# iDAC1.net
KiCad netlist of a schematic drawn in Altium Designer
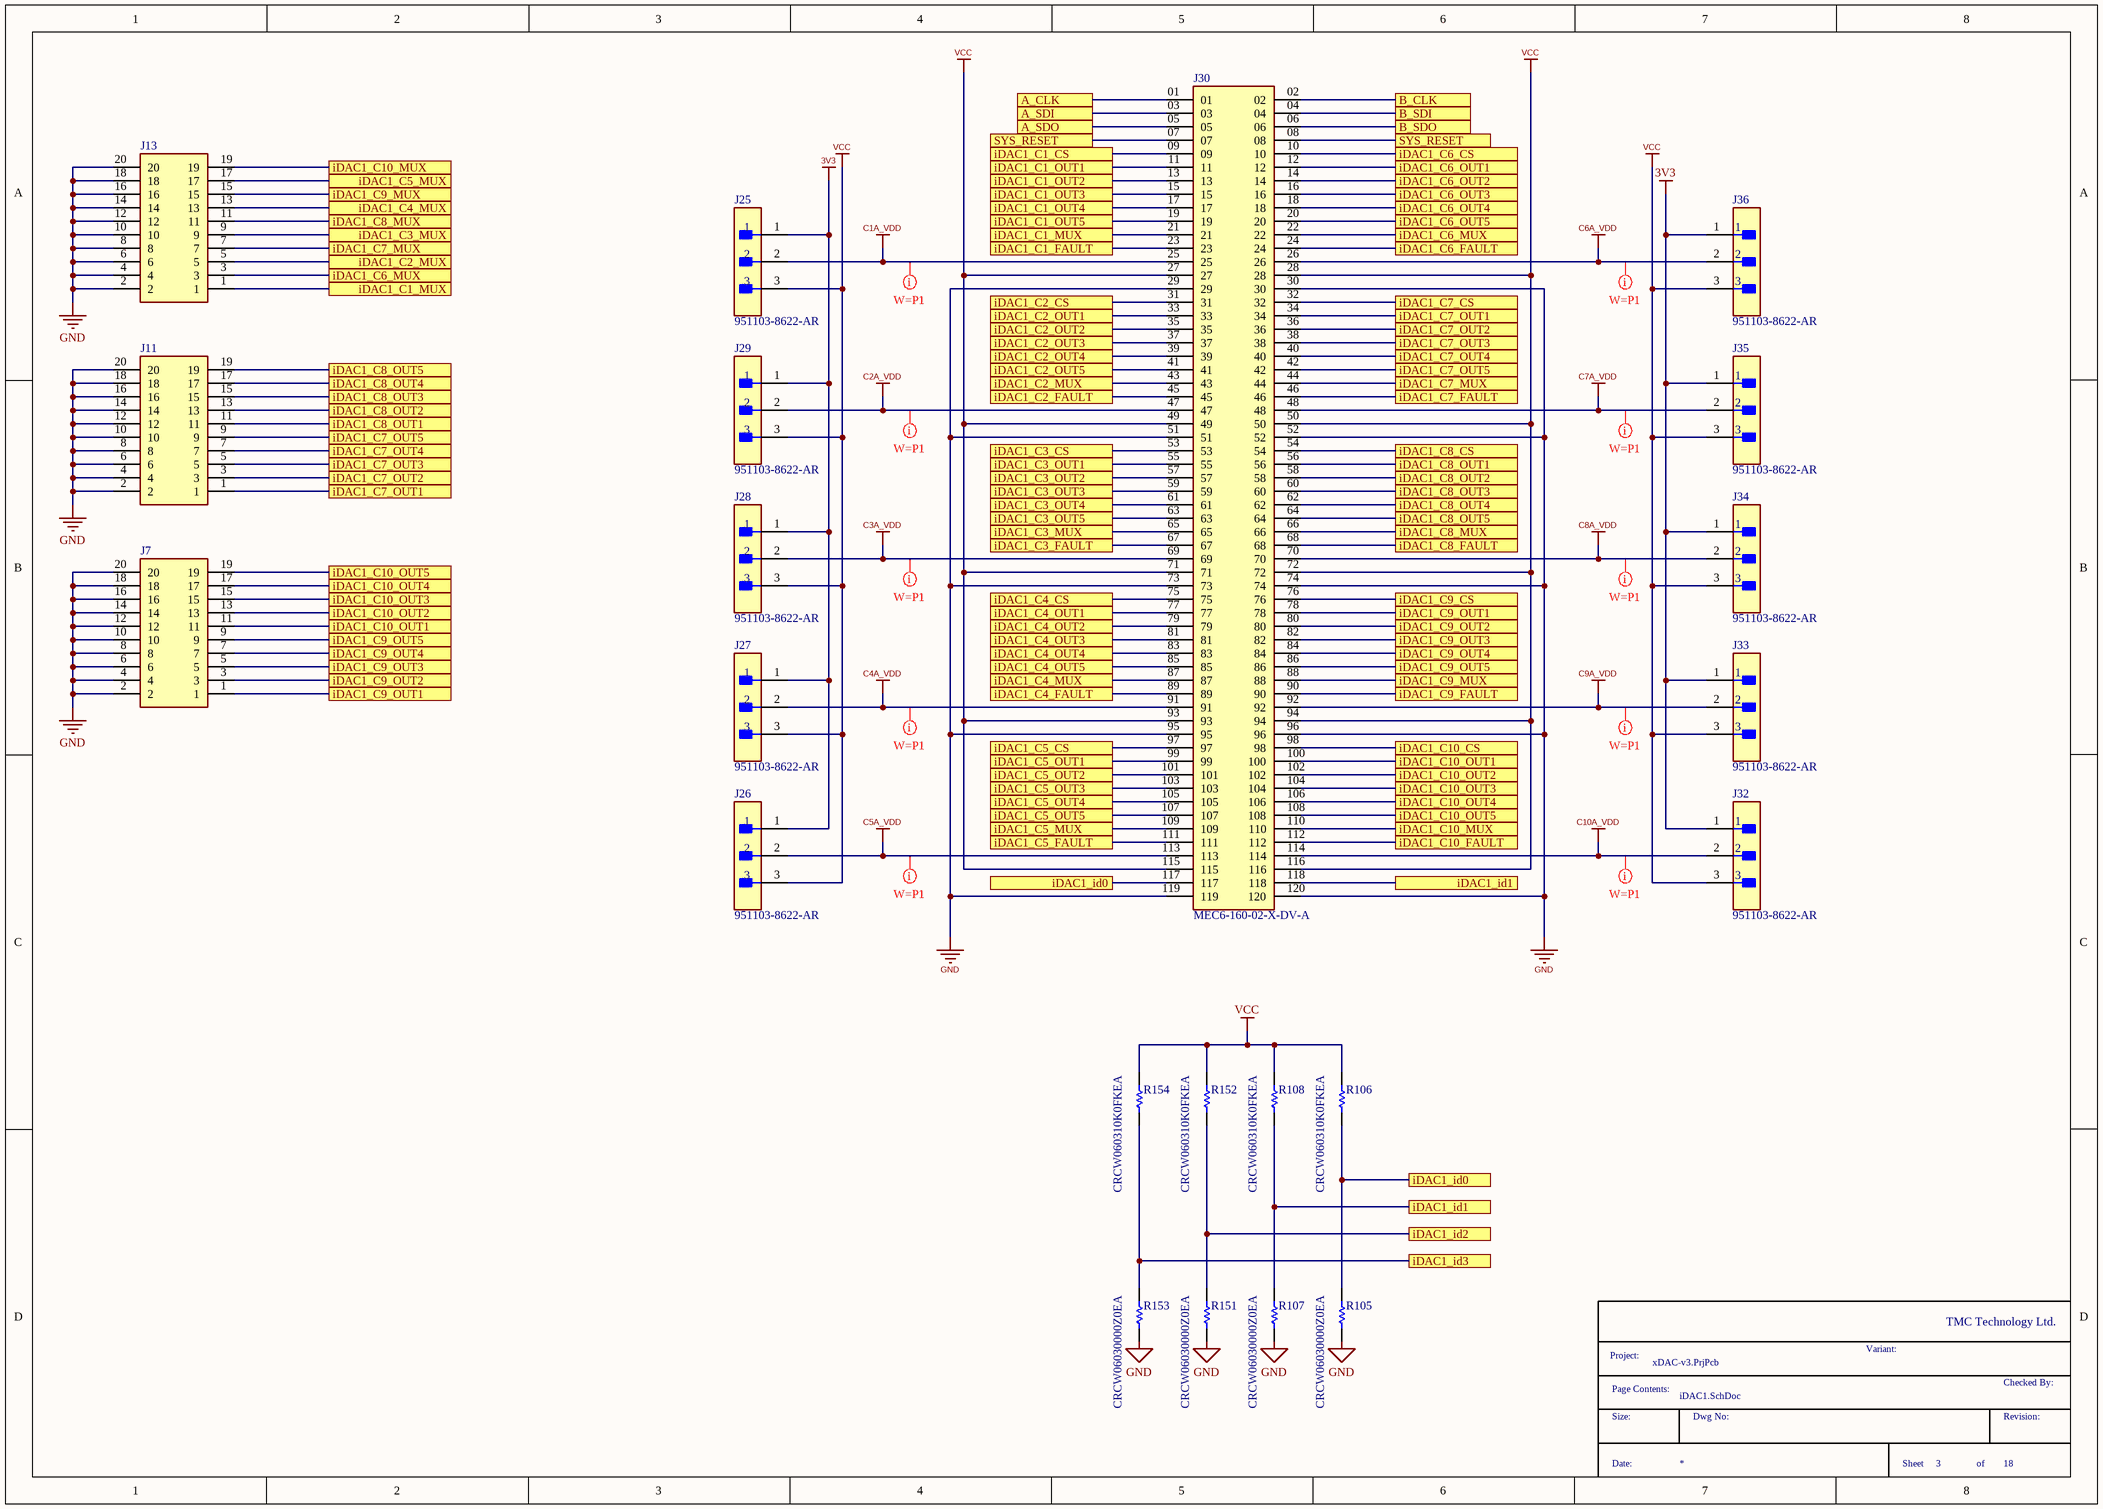
[diagram p0: iDAC1.SchDoc]

(export (version "E")
  (design (tool "Eeschema 10.0.6"))
  (components
    (comp (ref "J7")
      (value "~")
      (footprint "HDRV20W40P127_2X10_1270X340X550P")
      (description "Connector")
      (fields (field (name "MANUFACTURER_PART_NUMBER") "20021111-00020T4LF"))
      (libsource (lib "xDAC_Carrier") (part "20021111-00020T4LF"))
    )
    (comp (ref "J11")
      (value "~")
      (footprint "HDRV20W40P127_2X10_1270X340X550P")
      (description "Connector")
      (fields (field (name "MANUFACTURER_PART_NUMBER") "20021111-00020T4LF"))
      (libsource (lib "xDAC_Carrier") (part "20021111-00020T4LF"))
    )
    (comp (ref "J13")
      (value "~")
      (footprint "HDRV20W40P127_2X10_1270X340X550P")
      (description "Connector")
      (fields (field (name "MANUFACTURER_PART_NUMBER") "20021111-00020T4LF"))
      (libsource (lib "xDAC_Carrier") (part "20021111-00020T4LF"))
    )
    (comp (ref "J25")
      (value "951103-8622-AR")
      (footprint "FP-951103-8622-AR-MFG")
      (description "CONN HEADER VERT 3POS 2MM")
      (fields
        (field (name "OCTOPART") "https://octopart.com/951103-8622-ar-3m-14400669")
        (field (name "MANUFACTURER") "3M")
      )
      (libsource (lib "xDAC_Carrier") (part "CMP-05379-000003-1"))
    )
    (comp (ref "J26")
      (value "951103-8622-AR")
      (footprint "FP-951103-8622-AR-MFG")
      (description "CONN HEADER VERT 3POS 2MM")
      (fields
        (field (name "OCTOPART") "https://octopart.com/951103-8622-ar-3m-14400669")
        (field (name "MANUFACTURER") "3M")
      )
      (libsource (lib "xDAC_Carrier") (part "CMP-05379-000003-1"))
    )
    (comp (ref "J27")
      (value "951103-8622-AR")
      (footprint "FP-951103-8622-AR-MFG")
      (description "CONN HEADER VERT 3POS 2MM")
      (fields
        (field (name "OCTOPART") "https://octopart.com/951103-8622-ar-3m-14400669")
        (field (name "MANUFACTURER") "3M")
      )
      (libsource (lib "xDAC_Carrier") (part "CMP-05379-000003-1"))
    )
    (comp (ref "J28")
      (value "951103-8622-AR")
      (footprint "FP-951103-8622-AR-MFG")
      (description "CONN HEADER VERT 3POS 2MM")
      (fields
        (field (name "OCTOPART") "https://octopart.com/951103-8622-ar-3m-14400669")
        (field (name "MANUFACTURER") "3M")
      )
      (libsource (lib "xDAC_Carrier") (part "CMP-05379-000003-1"))
    )
    (comp (ref "J29")
      (value "951103-8622-AR")
      (footprint "FP-951103-8622-AR-MFG")
      (description "CONN HEADER VERT 3POS 2MM")
      (fields
        (field (name "OCTOPART") "https://octopart.com/951103-8622-ar-3m-14400669")
        (field (name "MANUFACTURER") "3M")
      )
      (libsource (lib "xDAC_Carrier") (part "CMP-05379-000003-1"))
    )
    (comp (ref "J30")
      (value "MEC6-160-02-X-DV-A")
      (footprint "SAMTEC_MEC6-160-02-X-DV-A")
      (fields (field (name "MF") "Samtec Inc."))
      (libsource (lib "xDAC_Carrier") (part "MEC6-160-02-X-DV-A"))
    )
    (comp (ref "J32")
      (value "951103-8622-AR")
      (footprint "FP-951103-8622-AR-MFG")
      (description "CONN HEADER VERT 3POS 2MM")
      (fields
        (field (name "OCTOPART") "https://octopart.com/951103-8622-ar-3m-14400669")
        (field (name "MANUFACTURER") "3M")
      )
      (libsource (lib "") (part "CMP-05379-000003-1_1"))
    )
    (comp (ref "J33")
      (value "951103-8622-AR")
      (footprint "FP-951103-8622-AR-MFG")
      (description "CONN HEADER VERT 3POS 2MM")
      (fields
        (field (name "OCTOPART") "https://octopart.com/951103-8622-ar-3m-14400669")
        (field (name "MANUFACTURER") "3M")
      )
      (libsource (lib "") (part "CMP-05379-000003-1_1"))
    )
    (comp (ref "J34")
      (value "951103-8622-AR")
      (footprint "FP-951103-8622-AR-MFG")
      (description "CONN HEADER VERT 3POS 2MM")
      (fields
        (field (name "OCTOPART") "https://octopart.com/951103-8622-ar-3m-14400669")
        (field (name "MANUFACTURER") "3M")
      )
      (libsource (lib "") (part "CMP-05379-000003-1_1"))
    )
    (comp (ref "J35")
      (value "951103-8622-AR")
      (footprint "FP-951103-8622-AR-MFG")
      (description "CONN HEADER VERT 3POS 2MM")
      (fields
        (field (name "OCTOPART") "https://octopart.com/951103-8622-ar-3m-14400669")
        (field (name "MANUFACTURER") "3M")
      )
      (libsource (lib "") (part "CMP-05379-000003-1_1"))
    )
    (comp (ref "J36")
      (value "951103-8622-AR")
      (footprint "FP-951103-8622-AR-MFG")
      (description "CONN HEADER VERT 3POS 2MM")
      (fields
        (field (name "OCTOPART") "https://octopart.com/951103-8622-ar-3m-14400669")
        (field (name "MANUFACTURER") "3M")
      )
      (libsource (lib "") (part "CMP-05379-000003-1_1"))
    )
    (comp (ref "R105")
      (value "CRCW06030000Z0EA")
      (footprint "RESC1609X50X30NL8T20")
      (description "Chip Resistor, 0 Ohm, Jumper, 100 mW, -55 to 155 degC, 0603 (1608 Metric), RoHS, Tape and Reel")
      (fields (field (name "MANUFACTURER") "Vishay Semiconductor"))
      (libsource (lib "Altium Content Vault") (part "RES-2"))
    )
    (comp (ref "R106")
      (value "CRCW060310K0FKEA")
      (footprint "RESC1609X50X30NL8T20")
      (description "Chip Resistor, 10 KOhm, +/- 1%, 100 mW, -55 to 155 degC, 0603 (1608 Metric), RoHS, Tape and Reel")
      (fields (field (name "MANUFACTURER") "Vishay Semiconductor"))
      (libsource (lib "Altium Content Vault") (part "RES-2"))
    )
    (comp (ref "R107")
      (value "CRCW06030000Z0EA")
      (footprint "RESC1609X50X30NL8T20")
      (description "Chip Resistor, 0 Ohm, Jumper, 100 mW, -55 to 155 degC, 0603 (1608 Metric), RoHS, Tape and Reel")
      (fields (field (name "MANUFACTURER") "Vishay Semiconductor"))
      (libsource (lib "Altium Content Vault") (part "RES-2"))
    )
    (comp (ref "R108")
      (value "CRCW060310K0FKEA")
      (footprint "RESC1609X50X30NL8T20")
      (description "Chip Resistor, 10 KOhm, +/- 1%, 100 mW, -55 to 155 degC, 0603 (1608 Metric), RoHS, Tape and Reel")
      (fields (field (name "MANUFACTURER") "Vishay Semiconductor"))
      (libsource (lib "Altium Content Vault") (part "RES-2"))
    )
    (comp (ref "R151")
      (value "CRCW06030000Z0EA")
      (footprint "RESC1609X50X30NL8T20")
      (description "Chip Resistor, 0 Ohm, Jumper, 100 mW, -55 to 155 degC, 0603 (1608 Metric), RoHS, Tape and Reel")
      (fields (field (name "MANUFACTURER") "Vishay Semiconductor"))
      (libsource (lib "Altium Content Vault") (part "RES-2"))
    )
    (comp (ref "R152")
      (value "CRCW060310K0FKEA")
      (footprint "RESC1609X50X30NL8T20")
      (description "Chip Resistor, 10 KOhm, +/- 1%, 100 mW, -55 to 155 degC, 0603 (1608 Metric), RoHS, Tape and Reel")
      (fields (field (name "MANUFACTURER") "Vishay Semiconductor"))
      (libsource (lib "Altium Content Vault") (part "RES-2"))
    )
    (comp (ref "R153")
      (value "CRCW06030000Z0EA")
      (footprint "RESC1609X50X30NL8T20")
      (description "Chip Resistor, 0 Ohm, Jumper, 100 mW, -55 to 155 degC, 0603 (1608 Metric), RoHS, Tape and Reel")
      (fields (field (name "MANUFACTURER") "Vishay Semiconductor"))
      (libsource (lib "Altium Content Vault") (part "RES-2"))
    )
    (comp (ref "R154")
      (value "CRCW060310K0FKEA")
      (footprint "RESC1609X50X30NL8T20")
      (description "Chip Resistor, 10 KOhm, +/- 1%, 100 mW, -55 to 155 degC, 0603 (1608 Metric), RoHS, Tape and Reel")
      (fields (field (name "MANUFACTURER") "Vishay Semiconductor"))
      (libsource (lib "Altium Content Vault") (part "RES-2"))
    )
  )
  (nets
    (net (code "1") (name "/A_CLK") (class "Default")
      (node (ref "J30") (pin "01") (pinfunction "01_01") (pintype "passive"))
    )
    (net (code "2") (name "/A_SDI") (class "Default")
      (node (ref "J30") (pin "03") (pinfunction "03_03") (pintype "passive"))
    )
    (net (code "3") (name "/A_SDO") (class "Default")
      (node (ref "J30") (pin "05") (pinfunction "05_05") (pintype "passive"))
    )
    (net (code "4") (name "/B_CLK") (class "Default")
      (node (ref "J30") (pin "02") (pinfunction "02_02") (pintype "passive"))
    )
    (net (code "5") (name "/B_SDI") (class "Default")
      (node (ref "J30") (pin "04") (pinfunction "04_04") (pintype "passive"))
    )
    (net (code "6") (name "/B_SDO") (class "Default")
      (node (ref "J30") (pin "06") (pinfunction "06_06") (pintype "passive"))
    )
    (net (code "7") (name "/SYS_RESET") (class "Default")
      (node (ref "J30") (pin "07") (pinfunction "07_07") (pintype "passive"))
      (node (ref "J30") (pin "08") (pinfunction "08_08") (pintype "passive"))
    )
    (net (code "8") (name "/iDAC1_C1_CS") (class "Default")
      (node (ref "J30") (pin "09") (pinfunction "09_09") (pintype "passive"))
    )
    (net (code "9") (name "/iDAC1_C1_FAULT") (class "Default")
      (node (ref "J30") (pin "23") (pinfunction "23_23") (pintype "passive"))
    )
    (net (code "10") (name "/iDAC1_C1_MUX") (class "Default")
      (node (ref "J13") (pin "1") (pinfunction "1_1") (pintype "passive"))
      (node (ref "J30") (pin "21") (pinfunction "21_21") (pintype "passive"))
    )
    (net (code "11") (name "/iDAC1_C1_OUT1") (class "Default")
      (node (ref "J30") (pin "11") (pinfunction "11_11") (pintype "passive"))
    )
    (net (code "12") (name "/iDAC1_C1_OUT2") (class "Default")
      (node (ref "J30") (pin "13") (pinfunction "13_13") (pintype "passive"))
    )
    (net (code "13") (name "/iDAC1_C1_OUT3") (class "Default")
      (node (ref "J30") (pin "15") (pinfunction "15_15") (pintype "passive"))
    )
    (net (code "14") (name "/iDAC1_C1_OUT4") (class "Default")
      (node (ref "J30") (pin "17") (pinfunction "17_17") (pintype "passive"))
    )
    (net (code "15") (name "/iDAC1_C1_OUT5") (class "Default")
      (node (ref "J30") (pin "19") (pinfunction "19_19") (pintype "passive"))
    )
    (net (code "16") (name "/iDAC1_C2_CS") (class "Default")
      (node (ref "J30") (pin "31") (pinfunction "31_31") (pintype "passive"))
    )
    (net (code "17") (name "/iDAC1_C2_FAULT") (class "Default")
      (node (ref "J30") (pin "45") (pinfunction "45_45") (pintype "passive"))
    )
    (net (code "18") (name "/iDAC1_C2_MUX") (class "Default")
      (node (ref "J13") (pin "5") (pinfunction "5_5") (pintype "passive"))
      (node (ref "J30") (pin "43") (pinfunction "43_43") (pintype "passive"))
    )
    (net (code "19") (name "/iDAC1_C2_OUT1") (class "Default")
      (node (ref "J30") (pin "33") (pinfunction "33_33") (pintype "passive"))
    )
    (net (code "20") (name "/iDAC1_C2_OUT2") (class "Default")
      (node (ref "J30") (pin "35") (pinfunction "35_35") (pintype "passive"))
    )
    (net (code "21") (name "/iDAC1_C2_OUT3") (class "Default")
      (node (ref "J30") (pin "37") (pinfunction "37_37") (pintype "passive"))
    )
    (net (code "22") (name "/iDAC1_C2_OUT4") (class "Default")
      (node (ref "J30") (pin "39") (pinfunction "39_39") (pintype "passive"))
    )
    (net (code "23") (name "/iDAC1_C2_OUT5") (class "Default")
      (node (ref "J30") (pin "41") (pinfunction "41_41") (pintype "passive"))
    )
    (net (code "24") (name "/iDAC1_C3_CS") (class "Default")
      (node (ref "J30") (pin "53") (pinfunction "53_53") (pintype "passive"))
    )
    (net (code "25") (name "/iDAC1_C3_FAULT") (class "Default")
      (node (ref "J30") (pin "67") (pinfunction "67_67") (pintype "passive"))
    )
    (net (code "26") (name "/iDAC1_C3_MUX") (class "Default")
      (node (ref "J13") (pin "9") (pinfunction "9_9") (pintype "passive"))
      (node (ref "J30") (pin "65") (pinfunction "65_65") (pintype "passive"))
    )
    (net (code "27") (name "/iDAC1_C3_OUT1") (class "Default")
      (node (ref "J30") (pin "55") (pinfunction "55_55") (pintype "passive"))
    )
    (net (code "28") (name "/iDAC1_C3_OUT2") (class "Default")
      (node (ref "J30") (pin "57") (pinfunction "57_57") (pintype "passive"))
    )
    (net (code "29") (name "/iDAC1_C3_OUT3") (class "Default")
      (node (ref "J30") (pin "59") (pinfunction "59_59") (pintype "passive"))
    )
    (net (code "30") (name "/iDAC1_C3_OUT4") (class "Default")
      (node (ref "J30") (pin "61") (pinfunction "61_61") (pintype "passive"))
    )
    (net (code "31") (name "/iDAC1_C3_OUT5") (class "Default")
      (node (ref "J30") (pin "63") (pinfunction "63_63") (pintype "passive"))
    )
    (net (code "32") (name "/iDAC1_C4_CS") (class "Default")
      (node (ref "J30") (pin "75") (pinfunction "75_75") (pintype "passive"))
    )
    (net (code "33") (name "/iDAC1_C4_FAULT") (class "Default")
      (node (ref "J30") (pin "89") (pinfunction "89_89") (pintype "passive"))
    )
    (net (code "34") (name "/iDAC1_C4_MUX") (class "Default")
      (node (ref "J13") (pin "13") (pinfunction "13_13") (pintype "passive"))
      (node (ref "J30") (pin "87") (pinfunction "87_87") (pintype "passive"))
    )
    (net (code "35") (name "/iDAC1_C4_OUT1") (class "Default")
      (node (ref "J30") (pin "77") (pinfunction "77_77") (pintype "passive"))
    )
    (net (code "36") (name "/iDAC1_C4_OUT2") (class "Default")
      (node (ref "J30") (pin "79") (pinfunction "79_79") (pintype "passive"))
    )
    (net (code "37") (name "/iDAC1_C4_OUT3") (class "Default")
      (node (ref "J30") (pin "81") (pinfunction "81_81") (pintype "passive"))
    )
    (net (code "38") (name "/iDAC1_C4_OUT4") (class "Default")
      (node (ref "J30") (pin "83") (pinfunction "83_83") (pintype "passive"))
    )
    (net (code "39") (name "/iDAC1_C4_OUT5") (class "Default")
      (node (ref "J30") (pin "85") (pinfunction "85_85") (pintype "passive"))
    )
    (net (code "40") (name "/iDAC1_C5_CS") (class "Default")
      (node (ref "J30") (pin "97") (pinfunction "97_97") (pintype "passive"))
    )
    (net (code "41") (name "/iDAC1_C5_FAULT") (class "Default")
      (node (ref "J30") (pin "111") (pinfunction "111_111") (pintype "passive"))
    )
    (net (code "42") (name "/iDAC1_C5_MUX") (class "Default")
      (node (ref "J13") (pin "17") (pinfunction "17_17") (pintype "passive"))
      (node (ref "J30") (pin "109") (pinfunction "109_109") (pintype "passive"))
    )
    (net (code "43") (name "/iDAC1_C5_OUT1") (class "Default")
      (node (ref "J30") (pin "99") (pinfunction "99_99") (pintype "passive"))
    )
    (net (code "44") (name "/iDAC1_C5_OUT2") (class "Default")
      (node (ref "J30") (pin "101") (pinfunction "101_101") (pintype "passive"))
    )
    (net (code "45") (name "/iDAC1_C5_OUT3") (class "Default")
      (node (ref "J30") (pin "103") (pinfunction "103_103") (pintype "passive"))
    )
    (net (code "46") (name "/iDAC1_C5_OUT4") (class "Default")
      (node (ref "J30") (pin "105") (pinfunction "105_105") (pintype "passive"))
    )
    (net (code "47") (name "/iDAC1_C5_OUT5") (class "Default")
      (node (ref "J30") (pin "107") (pinfunction "107_107") (pintype "passive"))
    )
    (net (code "48") (name "/iDAC1_C6_CS") (class "Default")
      (node (ref "J30") (pin "10") (pinfunction "10_10") (pintype "passive"))
    )
    (net (code "49") (name "/iDAC1_C6_FAULT") (class "Default")
      (node (ref "J30") (pin "24") (pinfunction "24_24") (pintype "passive"))
    )
    (net (code "50") (name "/iDAC1_C6_MUX") (class "Default")
      (node (ref "J13") (pin "3") (pinfunction "3_3") (pintype "passive"))
      (node (ref "J30") (pin "22") (pinfunction "22_22") (pintype "passive"))
    )
    (net (code "51") (name "/iDAC1_C6_OUT1") (class "Default")
      (node (ref "J30") (pin "12") (pinfunction "12_12") (pintype "passive"))
    )
    (net (code "52") (name "/iDAC1_C6_OUT2") (class "Default")
      (node (ref "J30") (pin "14") (pinfunction "14_14") (pintype "passive"))
    )
    (net (code "53") (name "/iDAC1_C6_OUT3") (class "Default")
      (node (ref "J30") (pin "16") (pinfunction "16_16") (pintype "passive"))
    )
    (net (code "54") (name "/iDAC1_C6_OUT4") (class "Default")
      (node (ref "J30") (pin "18") (pinfunction "18_18") (pintype "passive"))
    )
    (net (code "55") (name "/iDAC1_C6_OUT5") (class "Default")
      (node (ref "J30") (pin "20") (pinfunction "20_20") (pintype "passive"))
    )
    (net (code "56") (name "/iDAC1_C7_CS") (class "Default")
      (node (ref "J30") (pin "32") (pinfunction "32_32") (pintype "passive"))
    )
    (net (code "57") (name "/iDAC1_C7_FAULT") (class "Default")
      (node (ref "J30") (pin "46") (pinfunction "46_46") (pintype "passive"))
    )
    (net (code "58") (name "/iDAC1_C7_MUX") (class "Default")
      (node (ref "J13") (pin "7") (pinfunction "7_7") (pintype "passive"))
      (node (ref "J30") (pin "44") (pinfunction "44_44") (pintype "passive"))
    )
    (net (code "59") (name "/iDAC1_C7_OUT1") (class "Default")
      (node (ref "J11") (pin "1") (pinfunction "1_1") (pintype "passive"))
      (node (ref "J30") (pin "34") (pinfunction "34_34") (pintype "passive"))
    )
    (net (code "60") (name "/iDAC1_C7_OUT2") (class "Default")
      (node (ref "J11") (pin "3") (pinfunction "3_3") (pintype "passive"))
      (node (ref "J30") (pin "36") (pinfunction "36_36") (pintype "passive"))
    )
    (net (code "61") (name "/iDAC1_C7_OUT3") (class "Default")
      (node (ref "J11") (pin "5") (pinfunction "5_5") (pintype "passive"))
      (node (ref "J30") (pin "38") (pinfunction "38_38") (pintype "passive"))
    )
    (net (code "62") (name "/iDAC1_C7_OUT4") (class "Default")
      (node (ref "J11") (pin "7") (pinfunction "7_7") (pintype "passive"))
      (node (ref "J30") (pin "40") (pinfunction "40_40") (pintype "passive"))
    )
    (net (code "63") (name "/iDAC1_C7_OUT5") (class "Default")
      (node (ref "J11") (pin "9") (pinfunction "9_9") (pintype "passive"))
      (node (ref "J30") (pin "42") (pinfunction "42_42") (pintype "passive"))
    )
    (net (code "64") (name "/iDAC1_C8_CS") (class "Default")
      (node (ref "J30") (pin "54") (pinfunction "54_54") (pintype "passive"))
    )
    (net (code "65") (name "/iDAC1_C8_FAULT") (class "Default")
      (node (ref "J30") (pin "68") (pinfunction "68_68") (pintype "passive"))
    )
    (net (code "66") (name "/iDAC1_C8_MUX") (class "Default")
      (node (ref "J13") (pin "11") (pinfunction "11_11") (pintype "passive"))
      (node (ref "J30") (pin "66") (pinfunction "66_66") (pintype "passive"))
    )
    (net (code "67") (name "/iDAC1_C8_OUT1") (class "Default")
      (node (ref "J11") (pin "11") (pinfunction "11_11") (pintype "passive"))
      (node (ref "J30") (pin "56") (pinfunction "56_56") (pintype "passive"))
    )
    (net (code "68") (name "/iDAC1_C8_OUT2") (class "Default")
      (node (ref "J11") (pin "13") (pinfunction "13_13") (pintype "passive"))
      (node (ref "J30") (pin "58") (pinfunction "58_58") (pintype "passive"))
    )
    (net (code "69") (name "/iDAC1_C8_OUT3") (class "Default")
      (node (ref "J11") (pin "15") (pinfunction "15_15") (pintype "passive"))
      (node (ref "J30") (pin "60") (pinfunction "60_60") (pintype "passive"))
    )
    (net (code "70") (name "/iDAC1_C8_OUT4") (class "Default")
      (node (ref "J11") (pin "17") (pinfunction "17_17") (pintype "passive"))
      (node (ref "J30") (pin "62") (pinfunction "62_62") (pintype "passive"))
    )
    (net (code "71") (name "/iDAC1_C8_OUT5") (class "Default")
      (node (ref "J11") (pin "19") (pinfunction "19_19") (pintype "passive"))
      (node (ref "J30") (pin "64") (pinfunction "64_64") (pintype "passive"))
    )
    (net (code "72") (name "/iDAC1_C9_CS") (class "Default")
      (node (ref "J30") (pin "76") (pinfunction "76_76") (pintype "passive"))
    )
    (net (code "73") (name "/iDAC1_C9_FAULT") (class "Default")
      (node (ref "J30") (pin "90") (pinfunction "90_90") (pintype "passive"))
    )
    (net (code "74") (name "/iDAC1_C9_MUX") (class "Default")
      (node (ref "J13") (pin "15") (pinfunction "15_15") (pintype "passive"))
      (node (ref "J30") (pin "88") (pinfunction "88_88") (pintype "passive"))
    )
    (net (code "75") (name "/iDAC1_C9_OUT1") (class "Default")
      (node (ref "J30") (pin "78") (pinfunction "78_78") (pintype "passive"))
      (node (ref "J7") (pin "1") (pinfunction "1_1") (pintype "passive"))
    )
    (net (code "76") (name "/iDAC1_C9_OUT2") (class "Default")
      (node (ref "J30") (pin "80") (pinfunction "80_80") (pintype "passive"))
      (node (ref "J7") (pin "3") (pinfunction "3_3") (pintype "passive"))
    )
    (net (code "77") (name "/iDAC1_C9_OUT3") (class "Default")
      (node (ref "J30") (pin "82") (pinfunction "82_82") (pintype "passive"))
      (node (ref "J7") (pin "5") (pinfunction "5_5") (pintype "passive"))
    )
    (net (code "78") (name "/iDAC1_C9_OUT4") (class "Default")
      (node (ref "J30") (pin "84") (pinfunction "84_84") (pintype "passive"))
      (node (ref "J7") (pin "7") (pinfunction "7_7") (pintype "passive"))
    )
    (net (code "79") (name "/iDAC1_C9_OUT5") (class "Default")
      (node (ref "J30") (pin "86") (pinfunction "86_86") (pintype "passive"))
      (node (ref "J7") (pin "9") (pinfunction "9_9") (pintype "passive"))
    )
    (net (code "80") (name "/iDAC1_C10_CS") (class "Default")
      (node (ref "J30") (pin "98") (pinfunction "98_98") (pintype "passive"))
    )
    (net (code "81") (name "/iDAC1_C10_FAULT") (class "Default")
      (node (ref "J30") (pin "112") (pinfunction "112_112") (pintype "passive"))
    )
    (net (code "82") (name "/iDAC1_C10_MUX") (class "Default")
      (node (ref "J13") (pin "19") (pinfunction "19_19") (pintype "passive"))
      (node (ref "J30") (pin "110") (pinfunction "110_110") (pintype "passive"))
    )
    (net (code "83") (name "/iDAC1_C10_OUT1") (class "Default")
      (node (ref "J30") (pin "100") (pinfunction "100_100") (pintype "passive"))
      (node (ref "J7") (pin "11") (pinfunction "11_11") (pintype "passive"))
    )
    (net (code "84") (name "/iDAC1_C10_OUT2") (class "Default")
      (node (ref "J30") (pin "102") (pinfunction "102_102") (pintype "passive"))
      (node (ref "J7") (pin "13") (pinfunction "13_13") (pintype "passive"))
    )
    (net (code "85") (name "/iDAC1_C10_OUT3") (class "Default")
      (node (ref "J30") (pin "104") (pinfunction "104_104") (pintype "passive"))
      (node (ref "J7") (pin "15") (pinfunction "15_15") (pintype "passive"))
    )
    (net (code "86") (name "/iDAC1_C10_OUT4") (class "Default")
      (node (ref "J30") (pin "106") (pinfunction "106_106") (pintype "passive"))
      (node (ref "J7") (pin "17") (pinfunction "17_17") (pintype "passive"))
    )
    (net (code "87") (name "/iDAC1_C10_OUT5") (class "Default")
      (node (ref "J30") (pin "108") (pinfunction "108_108") (pintype "passive"))
      (node (ref "J7") (pin "19") (pinfunction "19_19") (pintype "passive"))
    )
    (net (code "88") (name "/iDAC1_id0") (class "Default")
      (node (ref "J30") (pin "117") (pinfunction "117_117") (pintype "passive"))
      (node (ref "R105") (pin "2") (pinfunction "2_2") (pintype "passive"))
      (node (ref "R106") (pin "1") (pinfunction "1_1") (pintype "passive"))
    )
    (net (code "89") (name "/iDAC1_id1") (class "Default")
      (node (ref "J30") (pin "118") (pinfunction "118_118") (pintype "passive"))
      (node (ref "R107") (pin "2") (pinfunction "2_2") (pintype "passive"))
      (node (ref "R108") (pin "1") (pinfunction "1_1") (pintype "passive"))
    )
    (net (code "90") (name "/iDAC1_id2") (class "Default")
      (node (ref "R151") (pin "2") (pinfunction "2_2") (pintype "passive"))
      (node (ref "R152") (pin "1") (pinfunction "1_1") (pintype "passive"))
    )
    (net (code "91") (name "/iDAC1_id3") (class "Default")
      (node (ref "R153") (pin "2") (pinfunction "2_2") (pintype "passive"))
      (node (ref "R154") (pin "1") (pinfunction "1_1") (pintype "passive"))
    )
    (net (code "92") (name "3V3") (class "Default")
      (node (ref "J25") (pin "1") (pinfunction "1_1") (pintype "passive"))
      (node (ref "J26") (pin "1") (pinfunction "1_1") (pintype "passive"))
      (node (ref "J27") (pin "1") (pinfunction "1_1") (pintype "passive"))
      (node (ref "J28") (pin "1") (pinfunction "1_1") (pintype "passive"))
      (node (ref "J29") (pin "1") (pinfunction "1_1") (pintype "passive"))
      (node (ref "J32") (pin "1") (pinfunction "1_1") (pintype "passive"))
      (node (ref "J33") (pin "1") (pinfunction "1_1") (pintype "passive"))
      (node (ref "J34") (pin "1") (pinfunction "1_1") (pintype "passive"))
      (node (ref "J35") (pin "1") (pinfunction "1_1") (pintype "passive"))
      (node (ref "J36") (pin "1") (pinfunction "1_1") (pintype "passive"))
    )
    (net (code "93") (name "C1A_VDD") (class "Default")
      (node (ref "J25") (pin "2") (pinfunction "2_2") (pintype "passive"))
      (node (ref "J30") (pin "25") (pinfunction "25_25") (pintype "passive"))
    )
    (net (code "94") (name "C2A_VDD") (class "Default")
      (node (ref "J29") (pin "2") (pinfunction "2_2") (pintype "passive"))
      (node (ref "J30") (pin "47") (pinfunction "47_47") (pintype "passive"))
    )
    (net (code "95") (name "C3A_VDD") (class "Default")
      (node (ref "J28") (pin "2") (pinfunction "2_2") (pintype "passive"))
      (node (ref "J30") (pin "69") (pinfunction "69_69") (pintype "passive"))
    )
    (net (code "96") (name "C4A_VDD") (class "Default")
      (node (ref "J27") (pin "2") (pinfunction "2_2") (pintype "passive"))
      (node (ref "J30") (pin "91") (pinfunction "91_91") (pintype "passive"))
    )
    (net (code "97") (name "C5A_VDD") (class "Default")
      (node (ref "J26") (pin "2") (pinfunction "2_2") (pintype "passive"))
      (node (ref "J30") (pin "113") (pinfunction "113_113") (pintype "passive"))
    )
    (net (code "98") (name "C6A_VDD") (class "Default")
      (node (ref "J30") (pin "26") (pinfunction "26_26") (pintype "passive"))
      (node (ref "J36") (pin "2") (pinfunction "2_2") (pintype "passive"))
    )
    (net (code "99") (name "C7A_VDD") (class "Default")
      (node (ref "J30") (pin "48") (pinfunction "48_48") (pintype "passive"))
      (node (ref "J35") (pin "2") (pinfunction "2_2") (pintype "passive"))
    )
    (net (code "100") (name "C8A_VDD") (class "Default")
      (node (ref "J30") (pin "70") (pinfunction "70_70") (pintype "passive"))
      (node (ref "J34") (pin "2") (pinfunction "2_2") (pintype "passive"))
    )
    (net (code "101") (name "C9A_VDD") (class "Default")
      (node (ref "J30") (pin "92") (pinfunction "92_92") (pintype "passive"))
      (node (ref "J33") (pin "2") (pinfunction "2_2") (pintype "passive"))
    )
    (net (code "102") (name "C10A_VDD") (class "Default")
      (node (ref "J30") (pin "114") (pinfunction "114_114") (pintype "passive"))
      (node (ref "J32") (pin "2") (pinfunction "2_2") (pintype "passive"))
    )
    (net (code "103") (name "GND") (class "Default")
      (node (ref "J11") (pin "10") (pinfunction "10_10") (pintype "passive"))
      (node (ref "J11") (pin "12") (pinfunction "12_12") (pintype "passive"))
      (node (ref "J11") (pin "14") (pinfunction "14_14") (pintype "passive"))
      (node (ref "J11") (pin "16") (pinfunction "16_16") (pintype "passive"))
      (node (ref "J11") (pin "18") (pinfunction "18_18") (pintype "passive"))
      (node (ref "J11") (pin "2") (pinfunction "2_2") (pintype "passive"))
      (node (ref "J11") (pin "20") (pinfunction "20_20") (pintype "passive"))
      (node (ref "J11") (pin "4") (pinfunction "4_4") (pintype "passive"))
      (node (ref "J11") (pin "6") (pinfunction "6_6") (pintype "passive"))
      (node (ref "J11") (pin "8") (pinfunction "8_8") (pintype "passive"))
      (node (ref "J13") (pin "10") (pinfunction "10_10") (pintype "passive"))
      (node (ref "J13") (pin "12") (pinfunction "12_12") (pintype "passive"))
      (node (ref "J13") (pin "14") (pinfunction "14_14") (pintype "passive"))
      (node (ref "J13") (pin "16") (pinfunction "16_16") (pintype "passive"))
      (node (ref "J13") (pin "18") (pinfunction "18_18") (pintype "passive"))
      (node (ref "J13") (pin "2") (pinfunction "2_2") (pintype "passive"))
      (node (ref "J13") (pin "20") (pinfunction "20_20") (pintype "passive"))
      (node (ref "J13") (pin "4") (pinfunction "4_4") (pintype "passive"))
      (node (ref "J13") (pin "6") (pinfunction "6_6") (pintype "passive"))
      (node (ref "J13") (pin "8") (pinfunction "8_8") (pintype "passive"))
      (node (ref "J30") (pin "119") (pinfunction "119_119") (pintype "passive"))
      (node (ref "J30") (pin "120") (pinfunction "120_120") (pintype "passive"))
      (node (ref "J30") (pin "29") (pinfunction "29_29") (pintype "passive"))
      (node (ref "J30") (pin "30") (pinfunction "30_30") (pintype "passive"))
      (node (ref "J30") (pin "51") (pinfunction "51_51") (pintype "passive"))
      (node (ref "J30") (pin "52") (pinfunction "52_52") (pintype "passive"))
      (node (ref "J30") (pin "73") (pinfunction "73_73") (pintype "passive"))
      (node (ref "J30") (pin "74") (pinfunction "74_74") (pintype "passive"))
      (node (ref "J30") (pin "95") (pinfunction "95_95") (pintype "passive"))
      (node (ref "J30") (pin "96") (pinfunction "96_96") (pintype "passive"))
      (node (ref "J7") (pin "10") (pinfunction "10_10") (pintype "passive"))
      (node (ref "J7") (pin "12") (pinfunction "12_12") (pintype "passive"))
      (node (ref "J7") (pin "14") (pinfunction "14_14") (pintype "passive"))
      (node (ref "J7") (pin "16") (pinfunction "16_16") (pintype "passive"))
      (node (ref "J7") (pin "18") (pinfunction "18_18") (pintype "passive"))
      (node (ref "J7") (pin "2") (pinfunction "2_2") (pintype "passive"))
      (node (ref "J7") (pin "20") (pinfunction "20_20") (pintype "passive"))
      (node (ref "J7") (pin "4") (pinfunction "4_4") (pintype "passive"))
      (node (ref "J7") (pin "6") (pinfunction "6_6") (pintype "passive"))
      (node (ref "J7") (pin "8") (pinfunction "8_8") (pintype "passive"))
      (node (ref "R105") (pin "1") (pinfunction "1_1") (pintype "passive"))
      (node (ref "R107") (pin "1") (pinfunction "1_1") (pintype "passive"))
      (node (ref "R151") (pin "1") (pinfunction "1_1") (pintype "passive"))
      (node (ref "R153") (pin "1") (pinfunction "1_1") (pintype "passive"))
    )
    (net (code "104") (name "VCC") (class "Default")
      (node (ref "J25") (pin "3") (pinfunction "3_3") (pintype "passive"))
      (node (ref "J26") (pin "3") (pinfunction "3_3") (pintype "passive"))
      (node (ref "J27") (pin "3") (pinfunction "3_3") (pintype "passive"))
      (node (ref "J28") (pin "3") (pinfunction "3_3") (pintype "passive"))
      (node (ref "J29") (pin "3") (pinfunction "3_3") (pintype "passive"))
      (node (ref "J30") (pin "115") (pinfunction "115_115") (pintype "passive"))
      (node (ref "J30") (pin "116") (pinfunction "116_116") (pintype "passive"))
      (node (ref "J30") (pin "27") (pinfunction "27_27") (pintype "passive"))
      (node (ref "J30") (pin "28") (pinfunction "28_28") (pintype "passive"))
      (node (ref "J30") (pin "49") (pinfunction "49_49") (pintype "passive"))
      (node (ref "J30") (pin "50") (pinfunction "50_50") (pintype "passive"))
      (node (ref "J30") (pin "71") (pinfunction "71_71") (pintype "passive"))
      (node (ref "J30") (pin "72") (pinfunction "72_72") (pintype "passive"))
      (node (ref "J30") (pin "93") (pinfunction "93_93") (pintype "passive"))
      (node (ref "J30") (pin "94") (pinfunction "94_94") (pintype "passive"))
      (node (ref "J32") (pin "3") (pinfunction "3_3") (pintype "passive"))
      (node (ref "J33") (pin "3") (pinfunction "3_3") (pintype "passive"))
      (node (ref "J34") (pin "3") (pinfunction "3_3") (pintype "passive"))
      (node (ref "J35") (pin "3") (pinfunction "3_3") (pintype "passive"))
      (node (ref "J36") (pin "3") (pinfunction "3_3") (pintype "passive"))
      (node (ref "R106") (pin "2") (pinfunction "2_2") (pintype "passive"))
      (node (ref "R108") (pin "2") (pinfunction "2_2") (pintype "passive"))
      (node (ref "R152") (pin "2") (pinfunction "2_2") (pintype "passive"))
      (node (ref "R154") (pin "2") (pinfunction "2_2") (pintype "passive"))
    )
  )
)
